# Left_Ear_Board.net
KiCad netlist of a schematic drawn in EAGLE
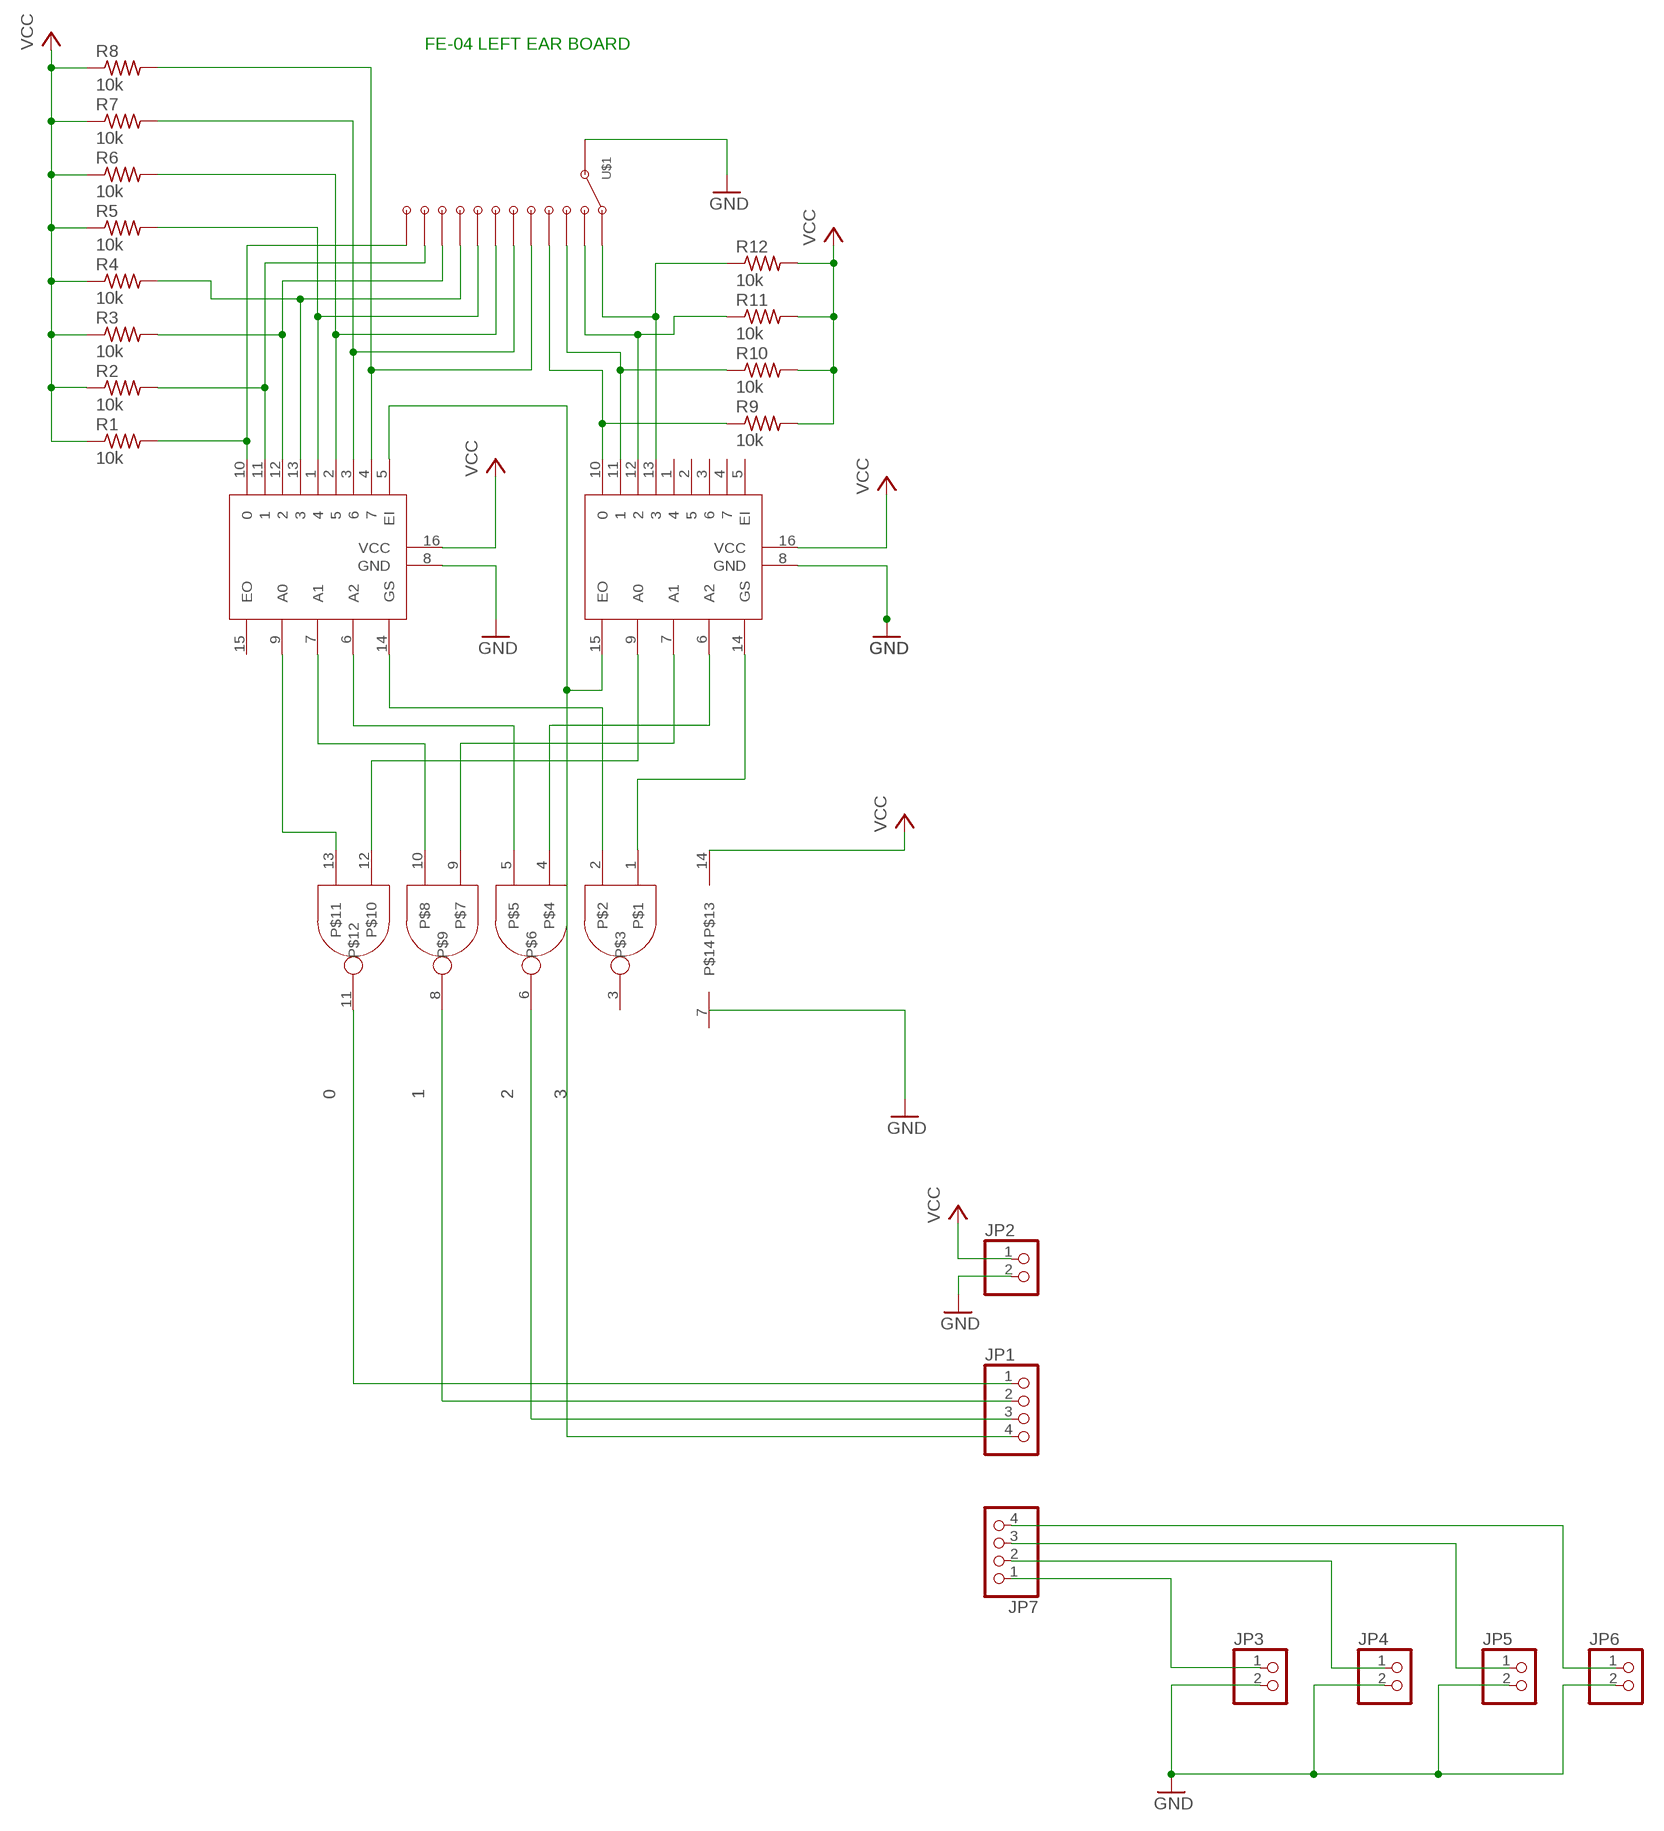
[diagram p0: schematic, sheet 1]

(export (version "E")
  (design (tool "Eeschema 10.0.6"))
  (components
    (comp (ref "JP1")
      (value "PINHD-1X4")
      (footprint "eagle-import:1X04")
      (libsource (lib "eagle-import") (part "PINHD-1X4"))
    )
    (comp (ref "JP2")
      (value "PINHD-1X2")
      (footprint "eagle-import:1X02")
      (libsource (lib "eagle-import") (part "PINHD-1X2"))
    )
    (comp (ref "JP3")
      (value "PINHD-1X2")
      (footprint "eagle-import:1X02")
      (libsource (lib "eagle-import") (part "PINHD-1X2"))
    )
    (comp (ref "JP4")
      (value "PINHD-1X2")
      (footprint "eagle-import:1X02")
      (libsource (lib "eagle-import") (part "PINHD-1X2"))
    )
    (comp (ref "JP5")
      (value "PINHD-1X2")
      (footprint "eagle-import:1X02")
      (libsource (lib "eagle-import") (part "PINHD-1X2"))
    )
    (comp (ref "JP6")
      (value "PINHD-1X2")
      (footprint "eagle-import:1X02")
      (libsource (lib "eagle-import") (part "PINHD-1X2"))
    )
    (comp (ref "JP7")
      (value "PINHD-1X4")
      (footprint "eagle-import:1X04")
      (libsource (lib "eagle-import") (part "PINHD-1X4"))
    )
    (comp (ref "R1")
      (value "10k")
      (footprint "eagle-import:R0603")
      (fields (field (name "PARTNO") "ERJ-3EKF2201V"))
      (libsource (lib "eagle-import") (part "R-US_R0603"))
    )
    (comp (ref "R2")
      (value "10k")
      (footprint "eagle-import:R0603")
      (fields (field (name "PARTNO") "ERJ-3EKF2201V"))
      (libsource (lib "eagle-import") (part "R-US_R0603"))
    )
    (comp (ref "R3")
      (value "10k")
      (footprint "eagle-import:R0603")
      (fields (field (name "PARTNO") "ERJ-3EKF2201V"))
      (libsource (lib "eagle-import") (part "R-US_R0603"))
    )
    (comp (ref "R4")
      (value "10k")
      (footprint "eagle-import:R0603")
      (fields (field (name "PARTNO") "ERJ-3EKF2201V"))
      (libsource (lib "eagle-import") (part "R-US_R0603"))
    )
    (comp (ref "R5")
      (value "10k")
      (footprint "eagle-import:R0603")
      (fields (field (name "PARTNO") "ERJ-3EKF2201V"))
      (libsource (lib "eagle-import") (part "R-US_R0603"))
    )
    (comp (ref "R6")
      (value "10k")
      (footprint "eagle-import:R0603")
      (fields (field (name "PARTNO") "ERJ-3EKF2201V"))
      (libsource (lib "eagle-import") (part "R-US_R0603"))
    )
    (comp (ref "R7")
      (value "10k")
      (footprint "eagle-import:R0603")
      (fields (field (name "PARTNO") "ERJ-3EKF2201V"))
      (libsource (lib "eagle-import") (part "R-US_R0603"))
    )
    (comp (ref "R8")
      (value "10k")
      (footprint "eagle-import:R0603")
      (fields (field (name "PARTNO") "ERJ-3EKF2201V"))
      (libsource (lib "eagle-import") (part "R-US_R0603"))
    )
    (comp (ref "R9")
      (value "10k")
      (footprint "eagle-import:R0603")
      (fields (field (name "PARTNO") "ERJ-3EKF2201V"))
      (libsource (lib "eagle-import") (part "R-US_R0603"))
    )
    (comp (ref "R10")
      (value "10k")
      (footprint "eagle-import:R0603")
      (fields (field (name "PARTNO") "ERJ-3EKF2201V"))
      (libsource (lib "eagle-import") (part "R-US_R0603"))
    )
    (comp (ref "R11")
      (value "10k")
      (footprint "eagle-import:R0603")
      (fields (field (name "PARTNO") "ERJ-3EKF2201V"))
      (libsource (lib "eagle-import") (part "R-US_R0603"))
    )
    (comp (ref "R12")
      (value "10k")
      (footprint "eagle-import:R0603")
      (fields (field (name "PARTNO") "ERJ-3EKF2201V"))
      (libsource (lib "eagle-import") (part "R-US_R0603"))
    )
    (comp (ref "U$1")
      (value "12-POSITION-ROTARY")
      (footprint "eagle-import:MC00L1NCQF")
      (libsource (lib "eagle-import") (part "12-POSITION-ROTARY"))
    )
    (comp (ref "U$2")
      (value "SN74LS148D")
      (footprint "eagle-import:SOIC-16")
      (libsource (lib "eagle-import") (part "SN74LS148D"))
    )
    (comp (ref "U$3")
      (value "SN74LS148D")
      (footprint "eagle-import:SOIC-16")
      (libsource (lib "eagle-import") (part "SN74LS148D"))
    )
    (comp (ref "U$4")
      (value "QUAD_NAND")
      (footprint "eagle-import:SOIC-14")
      (libsource (lib "eagle-import") (part "QUAD_NAND"))
    )
  )
  (nets
    (net (code "1") (name "/0") (class "Default")
      (node (ref "JP1") (pin "1") (pinfunction "1_1") (pintype "passive"))
      (node (ref "U$4") (pin "11") (pinfunction "P$12_11") (pintype "bidirectional"))
    )
    (net (code "2") (name "/1") (class "Default")
      (node (ref "JP1") (pin "2") (pinfunction "2_2") (pintype "passive"))
      (node (ref "U$4") (pin "8") (pinfunction "P$9_8") (pintype "bidirectional"))
    )
    (net (code "3") (name "/2") (class "Default")
      (node (ref "JP1") (pin "3") (pinfunction "3_3") (pintype "passive"))
      (node (ref "U$4") (pin "6") (pinfunction "P$6_6") (pintype "bidirectional"))
    )
    (net (code "4") (name "/3") (class "Default")
      (node (ref "JP1") (pin "4") (pinfunction "4_4") (pintype "passive"))
      (node (ref "U$2") (pin "5") (pinfunction "EI_5") (pintype "input"))
      (node (ref "U$3") (pin "15") (pinfunction "EO_15") (pintype "bidirectional"))
    )
    (net (code "5") (name "GND") (class "Default")
      (node (ref "JP2") (pin "2") (pinfunction "2_2") (pintype "passive"))
      (node (ref "JP3") (pin "2") (pinfunction "2_2") (pintype "passive"))
      (node (ref "JP4") (pin "2") (pinfunction "2_2") (pintype "passive"))
      (node (ref "JP5") (pin "2") (pinfunction "2_2") (pintype "passive"))
      (node (ref "JP6") (pin "2") (pinfunction "2_2") (pintype "passive"))
      (node (ref "U$1") (pin "P$13") (pinfunction "WIPER_P$13") (pintype "bidirectional"))
      (node (ref "U$2") (pin "8") (pinfunction "GND_8") (pintype "bidirectional"))
      (node (ref "U$3") (pin "8") (pinfunction "GND_8") (pintype "bidirectional"))
    )
    (net (code "6") (name "Net-(JP3-Pad1)") (class "Default")
      (node (ref "JP3") (pin "1") (pinfunction "1_1") (pintype "passive"))
      (node (ref "JP7") (pin "1") (pinfunction "1_1") (pintype "passive"))
    )
    (net (code "7") (name "Net-(JP4-Pad1)") (class "Default")
      (node (ref "JP4") (pin "1") (pinfunction "1_1") (pintype "passive"))
      (node (ref "JP7") (pin "2") (pinfunction "2_2") (pintype "passive"))
    )
    (net (code "8") (name "Net-(JP5-Pad1)") (class "Default")
      (node (ref "JP5") (pin "1") (pinfunction "1_1") (pintype "passive"))
      (node (ref "JP7") (pin "3") (pinfunction "3_3") (pintype "passive"))
    )
    (net (code "9") (name "Net-(JP6-Pad1)") (class "Default")
      (node (ref "JP6") (pin "1") (pinfunction "1_1") (pintype "passive"))
      (node (ref "JP7") (pin "4") (pinfunction "4_4") (pintype "passive"))
    )
    (net (code "10") (name "Net-(U$1-PIN1)") (class "Default")
      (node (ref "R12") (pin "1") (pinfunction "1_1") (pintype "passive"))
      (node (ref "U$1") (pin "P$1") (pinfunction "PIN1_P$1") (pintype "bidirectional"))
      (node (ref "U$3") (pin "13") (pinfunction "3_13") (pintype "input"))
    )
    (net (code "11") (name "Net-(U$1-PIN2)") (class "Default")
      (node (ref "R11") (pin "1") (pinfunction "1_1") (pintype "passive"))
      (node (ref "U$1") (pin "P$2") (pinfunction "PIN2_P$2") (pintype "bidirectional"))
      (node (ref "U$3") (pin "12") (pinfunction "2_12") (pintype "input"))
    )
    (net (code "12") (name "Net-(U$1-PIN3)") (class "Default")
      (node (ref "R10") (pin "1") (pinfunction "1_1") (pintype "passive"))
      (node (ref "U$1") (pin "P$3") (pinfunction "PIN3_P$3") (pintype "bidirectional"))
      (node (ref "U$3") (pin "11") (pinfunction "1_11") (pintype "input"))
    )
    (net (code "13") (name "Net-(U$1-PIN4)") (class "Default")
      (node (ref "R9") (pin "1") (pinfunction "1_1") (pintype "passive"))
      (node (ref "U$1") (pin "P$4") (pinfunction "PIN4_P$4") (pintype "bidirectional"))
      (node (ref "U$3") (pin "10") (pinfunction "0_10") (pintype "input"))
    )
    (net (code "14") (name "Net-(U$1-PIN5)") (class "Default")
      (node (ref "R8") (pin "2") (pinfunction "2_2") (pintype "passive"))
      (node (ref "U$1") (pin "P$5") (pinfunction "PIN5_P$5") (pintype "bidirectional"))
      (node (ref "U$2") (pin "4") (pinfunction "7_4") (pintype "input"))
    )
    (net (code "15") (name "Net-(U$1-PIN6)") (class "Default")
      (node (ref "R7") (pin "2") (pinfunction "2_2") (pintype "passive"))
      (node (ref "U$1") (pin "P$6") (pinfunction "PIN6_P$6") (pintype "bidirectional"))
      (node (ref "U$2") (pin "3") (pinfunction "6_3") (pintype "input"))
    )
    (net (code "16") (name "Net-(U$1-PIN7)") (class "Default")
      (node (ref "R6") (pin "2") (pinfunction "2_2") (pintype "passive"))
      (node (ref "U$1") (pin "P$7") (pinfunction "PIN7_P$7") (pintype "bidirectional"))
      (node (ref "U$2") (pin "2") (pinfunction "5_2") (pintype "input"))
    )
    (net (code "17") (name "Net-(U$1-PIN8)") (class "Default")
      (node (ref "R5") (pin "2") (pinfunction "2_2") (pintype "passive"))
      (node (ref "U$1") (pin "P$8") (pinfunction "PIN8_P$8") (pintype "bidirectional"))
      (node (ref "U$2") (pin "1") (pinfunction "4_1") (pintype "input"))
    )
    (net (code "18") (name "Net-(U$1-PIN9)") (class "Default")
      (node (ref "R4") (pin "2") (pinfunction "2_2") (pintype "passive"))
      (node (ref "U$1") (pin "P$9") (pinfunction "PIN9_P$9") (pintype "bidirectional"))
      (node (ref "U$2") (pin "13") (pinfunction "3_13") (pintype "input"))
    )
    (net (code "19") (name "Net-(U$1-PIN10)") (class "Default")
      (node (ref "R3") (pin "2") (pinfunction "2_2") (pintype "passive"))
      (node (ref "U$1") (pin "P$10") (pinfunction "PIN10_P$10") (pintype "bidirectional"))
      (node (ref "U$2") (pin "12") (pinfunction "2_12") (pintype "input"))
    )
    (net (code "20") (name "Net-(U$1-PIN11)") (class "Default")
      (node (ref "R2") (pin "2") (pinfunction "2_2") (pintype "passive"))
      (node (ref "U$1") (pin "P$11") (pinfunction "PIN11_P$11") (pintype "bidirectional"))
      (node (ref "U$2") (pin "11") (pinfunction "1_11") (pintype "input"))
    )
    (net (code "21") (name "Net-(U$1-PIN12)") (class "Default")
      (node (ref "R1") (pin "2") (pinfunction "2_2") (pintype "passive"))
      (node (ref "U$1") (pin "P$12") (pinfunction "PIN12_P$12") (pintype "bidirectional"))
      (node (ref "U$2") (pin "10") (pinfunction "0_10") (pintype "input"))
    )
    (net (code "22") (name "Net-(U$2-A0)") (class "Default")
      (node (ref "U$2") (pin "9") (pinfunction "A0_9") (pintype "bidirectional"))
      (node (ref "U$4") (pin "13") (pinfunction "P$11_13") (pintype "bidirectional"))
    )
    (net (code "23") (name "Net-(U$2-A1)") (class "Default")
      (node (ref "U$2") (pin "7") (pinfunction "A1_7") (pintype "bidirectional"))
      (node (ref "U$4") (pin "10") (pinfunction "P$8_10") (pintype "bidirectional"))
    )
    (net (code "24") (name "Net-(U$2-A2)") (class "Default")
      (node (ref "U$2") (pin "6") (pinfunction "A2_6") (pintype "bidirectional"))
      (node (ref "U$4") (pin "5") (pinfunction "P$5_5") (pintype "bidirectional"))
    )
    (net (code "25") (name "Net-(U$2-GS)") (class "Default")
      (node (ref "U$2") (pin "14") (pinfunction "GS_14") (pintype "bidirectional"))
      (node (ref "U$4") (pin "2") (pinfunction "P$2_2") (pintype "bidirectional"))
    )
    (net (code "26") (name "Net-(U$3-A0)") (class "Default")
      (node (ref "U$3") (pin "9") (pinfunction "A0_9") (pintype "bidirectional"))
      (node (ref "U$4") (pin "12") (pinfunction "P$10_12") (pintype "bidirectional"))
    )
    (net (code "27") (name "Net-(U$3-A1)") (class "Default")
      (node (ref "U$3") (pin "7") (pinfunction "A1_7") (pintype "bidirectional"))
      (node (ref "U$4") (pin "9") (pinfunction "P$7_9") (pintype "bidirectional"))
    )
    (net (code "28") (name "Net-(U$3-A2)") (class "Default")
      (node (ref "U$3") (pin "6") (pinfunction "A2_6") (pintype "bidirectional"))
      (node (ref "U$4") (pin "4") (pinfunction "P$4_4") (pintype "bidirectional"))
    )
    (net (code "29") (name "Net-(U$3-GS)") (class "Default")
      (node (ref "U$3") (pin "14") (pinfunction "GS_14") (pintype "bidirectional"))
      (node (ref "U$4") (pin "1") (pinfunction "P$1_1") (pintype "bidirectional"))
    )
    (net (code "30") (name "VCC") (class "Default")
      (node (ref "JP2") (pin "1") (pinfunction "1_1") (pintype "passive"))
      (node (ref "R1") (pin "1") (pinfunction "1_1") (pintype "passive"))
      (node (ref "R10") (pin "2") (pinfunction "2_2") (pintype "passive"))
      (node (ref "R11") (pin "2") (pinfunction "2_2") (pintype "passive"))
      (node (ref "R12") (pin "2") (pinfunction "2_2") (pintype "passive"))
      (node (ref "R2") (pin "1") (pinfunction "1_1") (pintype "passive"))
      (node (ref "R3") (pin "1") (pinfunction "1_1") (pintype "passive"))
      (node (ref "R4") (pin "1") (pinfunction "1_1") (pintype "passive"))
      (node (ref "R5") (pin "1") (pinfunction "1_1") (pintype "passive"))
      (node (ref "R6") (pin "1") (pinfunction "1_1") (pintype "passive"))
      (node (ref "R7") (pin "1") (pinfunction "1_1") (pintype "passive"))
      (node (ref "R8") (pin "1") (pinfunction "1_1") (pintype "passive"))
      (node (ref "R9") (pin "2") (pinfunction "2_2") (pintype "passive"))
      (node (ref "U$2") (pin "16") (pinfunction "VCC_16") (pintype "bidirectional"))
      (node (ref "U$3") (pin "16") (pinfunction "VCC_16") (pintype "bidirectional"))
      (node (ref "U$4") (pin "14") (pinfunction "P$13_14") (pintype "bidirectional"))
    )
    (net (code "31") (name "unconnected-(U$2-EO-Pad15)") (class "Default")
      (node (ref "U$2") (pin "15") (pinfunction "EO_15") (pintype "bidirectional"))
    )
    (net (code "32") (name "unconnected-(U$3-4-Pad1)") (class "Default")
      (node (ref "U$3") (pin "1") (pinfunction "4_1") (pintype "input"))
    )
    (net (code "33") (name "unconnected-(U$3-5-Pad2)") (class "Default")
      (node (ref "U$3") (pin "2") (pinfunction "5_2") (pintype "input"))
    )
    (net (code "34") (name "unconnected-(U$3-6-Pad3)") (class "Default")
      (node (ref "U$3") (pin "3") (pinfunction "6_3") (pintype "input"))
    )
    (net (code "35") (name "unconnected-(U$3-7-Pad4)") (class "Default")
      (node (ref "U$3") (pin "4") (pinfunction "7_4") (pintype "input"))
    )
    (net (code "36") (name "unconnected-(U$3-EI-Pad5)") (class "Default")
      (node (ref "U$3") (pin "5") (pinfunction "EI_5") (pintype "input"))
    )
    (net (code "37") (name "unconnected-(U$4-P$3-Pad3)") (class "Default")
      (node (ref "U$4") (pin "3") (pinfunction "P$3_3") (pintype "bidirectional"))
    )
    (net (code "38") (name "unconnected-(U$4-P$14-Pad7)") (class "Default")
      (node (ref "U$4") (pin "7") (pinfunction "P$14_7") (pintype "bidirectional"))
    )
  )
)
